# schem.net
KiCad netlist of a schematic drawn in EAGLE
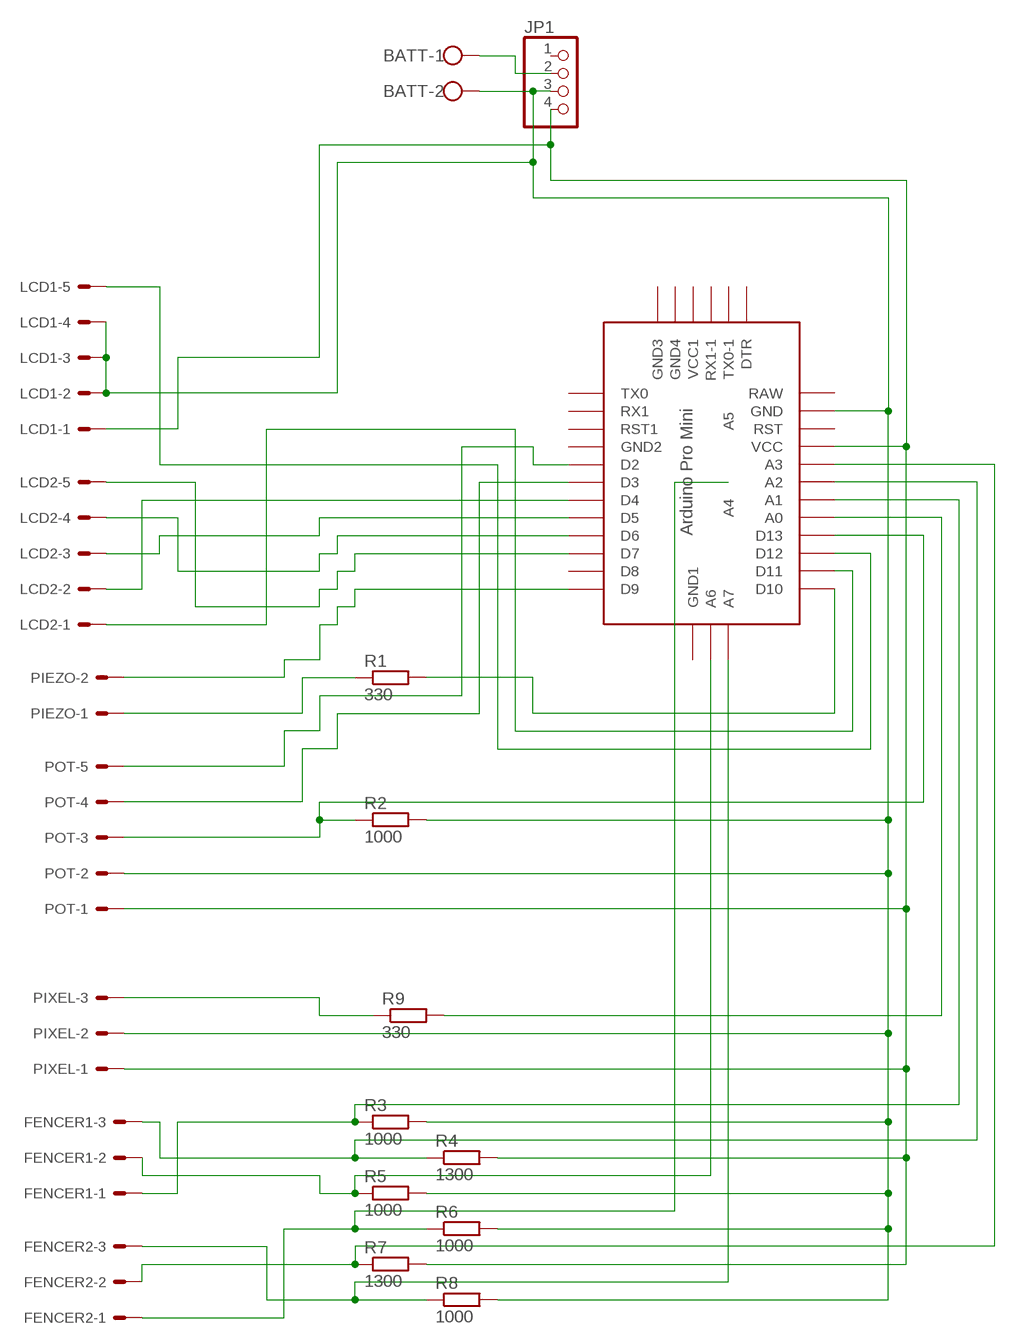
[diagram p0: schematic, sheet 1]

(export (version "E")
  (design (tool "Eeschema 10.0.6"))
  (components
    (comp (ref "BATT")
      (value "W237-102")
      (footprint "eagle-import:W237-102")
      (fields (field (name "MPN") "237-102"))
      (libsource (lib "eagle-import") (part "W237-102"))
    )
    (comp (ref "FENCER1")
      (value "22-27-2031-03")
      (footprint "eagle-import:6410-03")
      (libsource (lib "eagle-import") (part "22-?-0327-2031"))
    )
    (comp (ref "FENCER2")
      (value "22-27-2031-03")
      (footprint "eagle-import:6410-03")
      (libsource (lib "eagle-import") (part "22-?-0327-2031"))
    )
    (comp (ref "JP1")
      (value "PINHD-1X4")
      (footprint "eagle-import:1X04")
      (libsource (lib "eagle-import") (part "PINHD-1X4"))
    )
    (comp (ref "LCD1")
      (value "22-27-2051-05")
      (footprint "eagle-import:6410-05")
      (libsource (lib "eagle-import") (part "22-?-0527-2051"))
    )
    (comp (ref "LCD2")
      (value "22-27-2051-05")
      (footprint "eagle-import:6410-05")
      (libsource (lib "eagle-import") (part "22-?-0527-2051"))
    )
    (comp (ref "PIEZO")
      (value "22-27-2021-02")
      (footprint "eagle-import:6410-02")
      (libsource (lib "eagle-import") (part "22-?-0227-2021"))
    )
    (comp (ref "PIXEL")
      (value "22-27-2031-03")
      (footprint "eagle-import:6410-03")
      (libsource (lib "eagle-import") (part "22-?-0327-2031"))
    )
    (comp (ref "POT")
      (value "22-27-2051-05")
      (footprint "eagle-import:6410-05")
      (libsource (lib "eagle-import") (part "22-?-0527-2051"))
    )
    (comp (ref "R1")
      (value "330")
      (footprint "eagle-import:0204_7")
      (libsource (lib "eagle-import") (part "R-EU_0204/7"))
    )
    (comp (ref "R2")
      (value "1000")
      (footprint "eagle-import:0204_7")
      (libsource (lib "eagle-import") (part "R-EU_0204/7"))
    )
    (comp (ref "R3")
      (value "1000")
      (footprint "eagle-import:0204_7")
      (libsource (lib "eagle-import") (part "R-EU_0204/7"))
    )
    (comp (ref "R4")
      (value "1300")
      (footprint "eagle-import:0204_7")
      (libsource (lib "eagle-import") (part "R-EU_0204/7"))
    )
    (comp (ref "R5")
      (value "1000")
      (footprint "eagle-import:0204_7")
      (libsource (lib "eagle-import") (part "R-EU_0204/7"))
    )
    (comp (ref "R6")
      (value "1000")
      (footprint "eagle-import:0204_7")
      (libsource (lib "eagle-import") (part "R-EU_0204/7"))
    )
    (comp (ref "R7")
      (value "1300")
      (footprint "eagle-import:0204_7")
      (libsource (lib "eagle-import") (part "R-EU_0204/7"))
    )
    (comp (ref "R8")
      (value "1000")
      (footprint "eagle-import:0204_7")
      (libsource (lib "eagle-import") (part "R-EU_0204/7"))
    )
    (comp (ref "R9")
      (value "330")
      (footprint "eagle-import:0207_10")
      (libsource (lib "eagle-import") (part "R-EU_0207/10"))
    )
    (comp (ref "U$1")
      (value "ABK-PRO-MINI")
      (footprint "eagle-import:ABK-PRO-MINI")
      (libsource (lib "eagle-import") (part "ABK-PRO-MINI"))
    )
  )
  (nets
    (net (code "1") (name "Net-(BATTA-KL)") (class "Default")
      (node (ref "BATT") (pin "1") (pinfunction "KL_1") (pintype "passive"))
      (node (ref "JP1") (pin "2") (pinfunction "2_2") (pintype "passive"))
    )
    (net (code "2") (name "Net-(BATTB-KL)") (class "Default")
      (node (ref "BATT") (pin "2") (pinfunction "KL_2") (pintype "passive"))
      (node (ref "JP1") (pin "3") (pinfunction "3_3") (pintype "passive"))
      (node (ref "LCD1") (pin "2") (pinfunction "S_2") (pintype "passive"))
      (node (ref "LCD1") (pin "3") (pinfunction "S_3") (pintype "passive"))
      (node (ref "LCD1") (pin "4") (pinfunction "S_4") (pintype "passive"))
      (node (ref "PIXEL") (pin "2") (pinfunction "S_2") (pintype "passive"))
      (node (ref "POT") (pin "2") (pinfunction "S_2") (pintype "passive"))
      (node (ref "R2") (pin "2") (pinfunction "2_2") (pintype "passive"))
      (node (ref "R3") (pin "2") (pinfunction "2_2") (pintype "passive"))
      (node (ref "R5") (pin "2") (pinfunction "2_2") (pintype "passive"))
      (node (ref "R6") (pin "2") (pinfunction "2_2") (pintype "passive"))
      (node (ref "R8") (pin "2") (pinfunction "2_2") (pintype "passive"))
      (node (ref "U$1") (pin "GND") (pinfunction "GND_GND") (pintype "bidirectional"))
    )
    (net (code "3") (name "Net-(FENCER1A-S)") (class "Default")
      (node (ref "FENCER1") (pin "1") (pinfunction "S_1") (pintype "passive"))
      (node (ref "R3") (pin "1") (pinfunction "1_1") (pintype "passive"))
      (node (ref "U$1") (pin "A1") (pinfunction "A1_A1") (pintype "bidirectional"))
    )
    (net (code "4") (name "Net-(FENCER1B-S)") (class "Default")
      (node (ref "FENCER1") (pin "2") (pinfunction "S_2") (pintype "passive"))
      (node (ref "R5") (pin "1") (pinfunction "1_1") (pintype "passive"))
      (node (ref "U$1") (pin "A6") (pinfunction "A6_A6") (pintype "bidirectional"))
    )
    (net (code "5") (name "Net-(FENCER1C-S)") (class "Default")
      (node (ref "FENCER1") (pin "3") (pinfunction "S_3") (pintype "passive"))
      (node (ref "R4") (pin "1") (pinfunction "1_1") (pintype "passive"))
      (node (ref "U$1") (pin "A2") (pinfunction "A2_A2") (pintype "bidirectional"))
    )
    (net (code "6") (name "Net-(FENCER2A-S)") (class "Default")
      (node (ref "FENCER2") (pin "1") (pinfunction "S_1") (pintype "passive"))
      (node (ref "R6") (pin "1") (pinfunction "1_1") (pintype "passive"))
      (node (ref "U$1") (pin "A4") (pinfunction "A4_A4") (pintype "bidirectional"))
    )
    (net (code "7") (name "Net-(FENCER2B-S)") (class "Default")
      (node (ref "FENCER2") (pin "2") (pinfunction "S_2") (pintype "passive"))
      (node (ref "R7") (pin "1") (pinfunction "1_1") (pintype "passive"))
      (node (ref "U$1") (pin "A3") (pinfunction "A3_A3") (pintype "bidirectional"))
    )
    (net (code "8") (name "Net-(FENCER2C-S)") (class "Default")
      (node (ref "FENCER2") (pin "3") (pinfunction "S_3") (pintype "passive"))
      (node (ref "R8") (pin "1") (pinfunction "1_1") (pintype "passive"))
      (node (ref "U$1") (pin "A7") (pinfunction "A7_A7") (pintype "bidirectional"))
    )
    (net (code "9") (name "Net-(LCD1A-S)") (class "Default")
      (node (ref "JP1") (pin "4") (pinfunction "4_4") (pintype "passive"))
      (node (ref "LCD1") (pin "1") (pinfunction "S_1") (pintype "passive"))
      (node (ref "PIXEL") (pin "1") (pinfunction "S_1") (pintype "passive"))
      (node (ref "POT") (pin "1") (pinfunction "S_1") (pintype "passive"))
      (node (ref "R4") (pin "2") (pinfunction "2_2") (pintype "passive"))
      (node (ref "R7") (pin "2") (pinfunction "2_2") (pintype "passive"))
      (node (ref "U$1") (pin "VCC") (pinfunction "VCC_VCC") (pintype "bidirectional"))
    )
    (net (code "10") (name "Net-(LCD1E-S)") (class "Default")
      (node (ref "LCD1") (pin "5") (pinfunction "S_5") (pintype "passive"))
      (node (ref "U$1") (pin "D12") (pinfunction "D12_D12") (pintype "bidirectional"))
    )
    (net (code "11") (name "Net-(LCD2A-S)") (class "Default")
      (node (ref "LCD2") (pin "1") (pinfunction "S_1") (pintype "passive"))
      (node (ref "U$1") (pin "D11") (pinfunction "D11_D11") (pintype "bidirectional"))
    )
    (net (code "12") (name "Net-(LCD2B-S)") (class "Default")
      (node (ref "LCD2") (pin "2") (pinfunction "S_2") (pintype "passive"))
      (node (ref "U$1") (pin "D4") (pinfunction "D4_D4") (pintype "bidirectional"))
    )
    (net (code "13") (name "Net-(LCD2C-S)") (class "Default")
      (node (ref "LCD2") (pin "3") (pinfunction "S_3") (pintype "passive"))
      (node (ref "U$1") (pin "D5") (pinfunction "D5_D5") (pintype "bidirectional"))
    )
    (net (code "14") (name "Net-(LCD2D-S)") (class "Default")
      (node (ref "LCD2") (pin "4") (pinfunction "S_4") (pintype "passive"))
      (node (ref "U$1") (pin "D6") (pinfunction "D6_D6") (pintype "bidirectional"))
    )
    (net (code "15") (name "Net-(LCD2E-S)") (class "Default")
      (node (ref "LCD2") (pin "5") (pinfunction "S_5") (pintype "passive"))
      (node (ref "U$1") (pin "D7") (pinfunction "D7_D7") (pintype "bidirectional"))
    )
    (net (code "16") (name "Net-(PIEZOA-S)") (class "Default")
      (node (ref "PIEZO") (pin "1") (pinfunction "S_1") (pintype "passive"))
      (node (ref "R1") (pin "1") (pinfunction "1_1") (pintype "passive"))
    )
    (net (code "17") (name "Net-(PIEZOB-S)") (class "Default")
      (node (ref "PIEZO") (pin "2") (pinfunction "S_2") (pintype "passive"))
      (node (ref "U$1") (pin "D9") (pinfunction "D9_D9") (pintype "bidirectional"))
    )
    (net (code "18") (name "Net-(PIXELC-S)") (class "Default")
      (node (ref "PIXEL") (pin "3") (pinfunction "S_3") (pintype "passive"))
      (node (ref "R9") (pin "1") (pinfunction "1_1") (pintype "passive"))
    )
    (net (code "19") (name "Net-(POTC-S)") (class "Default")
      (node (ref "POT") (pin "3") (pinfunction "S_3") (pintype "passive"))
      (node (ref "R2") (pin "1") (pinfunction "1_1") (pintype "passive"))
      (node (ref "U$1") (pin "D13") (pinfunction "D13_D13") (pintype "bidirectional"))
    )
    (net (code "20") (name "Net-(POTD-S)") (class "Default")
      (node (ref "POT") (pin "4") (pinfunction "S_4") (pintype "passive"))
      (node (ref "U$1") (pin "D3") (pinfunction "D3_D3") (pintype "bidirectional"))
    )
    (net (code "21") (name "Net-(POTE-S)") (class "Default")
      (node (ref "POT") (pin "5") (pinfunction "S_5") (pintype "passive"))
      (node (ref "U$1") (pin "D2") (pinfunction "D2_D2") (pintype "bidirectional"))
    )
    (net (code "22") (name "Net-(R1-Pad2)") (class "Default")
      (node (ref "R1") (pin "2") (pinfunction "2_2") (pintype "passive"))
      (node (ref "U$1") (pin "D10") (pinfunction "D10_D10") (pintype "bidirectional"))
    )
    (net (code "23") (name "Net-(R9-Pad2)") (class "Default")
      (node (ref "R9") (pin "2") (pinfunction "2_2") (pintype "passive"))
      (node (ref "U$1") (pin "A0") (pinfunction "A0_A0") (pintype "bidirectional"))
    )
    (net (code "24") (name "unconnected-(JP1-Pad1)") (class "Default")
      (node (ref "JP1") (pin "1") (pinfunction "1_1") (pintype "passive"))
    )
    (net (code "25") (name "unconnected-(U$1-GND1-PadGND4)") (class "Default")
      (node (ref "U$1") (pin "GND4") (pinfunction "GND1_GND4") (pintype "bidirectional"))
    )
    (net (code "26") (name "unconnected-(U$1-GND2-PadGND1)") (class "Default")
      (node (ref "U$1") (pin "GND1") (pinfunction "GND2_GND1") (pintype "bidirectional"))
    )
    (net (code "27") (name "unconnected-(U$1-GND3-PadGND2)") (class "Default")
      (node (ref "U$1") (pin "GND2") (pinfunction "GND3_GND2") (pintype "bidirectional"))
    )
    (net (code "28") (name "unconnected-(U$1-GND4-PadGND3)") (class "Default")
      (node (ref "U$1") (pin "GND3") (pinfunction "GND4_GND3") (pintype "bidirectional"))
    )
    (net (code "29") (name "unconnected-(U$1-PadA5)") (class "Default")
      (node (ref "U$1") (pin "A5") (pinfunction "A5_A5") (pintype "bidirectional"))
    )
    (net (code "30") (name "unconnected-(U$1-PadD8)") (class "Default")
      (node (ref "U$1") (pin "D8") (pinfunction "D8_D8") (pintype "bidirectional"))
    )
    (net (code "31") (name "unconnected-(U$1-PadDTR)") (class "Default")
      (node (ref "U$1") (pin "DTR") (pinfunction "DTR_DTR") (pintype "bidirectional"))
    )
    (net (code "32") (name "unconnected-(U$1-PadRAW)") (class "Default")
      (node (ref "U$1") (pin "RAW") (pinfunction "RAW_RAW") (pintype "bidirectional"))
    )
    (net (code "33") (name "unconnected-(U$1-PadRST)") (class "Default")
      (node (ref "U$1") (pin "RST") (pinfunction "RST_RST") (pintype "bidirectional"))
    )
    (net (code "34") (name "unconnected-(U$1-PadRST1)") (class "Default")
      (node (ref "U$1") (pin "RST1") (pinfunction "RST1_RST1") (pintype "bidirectional"))
    )
    (net (code "35") (name "unconnected-(U$1-PadRX1)") (class "Default")
      (node (ref "U$1") (pin "RX1") (pinfunction "RX1_RX1") (pintype "bidirectional"))
    )
    (net (code "36") (name "unconnected-(U$1-PadRX1-1)") (class "Default")
      (node (ref "U$1") (pin "RX1-1") (pinfunction "RX1-1_RX1-1") (pintype "bidirectional"))
    )
    (net (code "37") (name "unconnected-(U$1-PadTX0)") (class "Default")
      (node (ref "U$1") (pin "TX0") (pinfunction "TX0_TX0") (pintype "bidirectional"))
    )
    (net (code "38") (name "unconnected-(U$1-PadTX0-1)") (class "Default")
      (node (ref "U$1") (pin "TX0-1") (pinfunction "TX0-1_TX0-1") (pintype "bidirectional"))
    )
    (net (code "39") (name "unconnected-(U$1-PadVCC1)") (class "Default")
      (node (ref "U$1") (pin "VCC1") (pinfunction "VCC1_VCC1") (pintype "bidirectional"))
    )
  )
)
